# manual_motors.net
KiCad netlist of a schematic drawn in EAGLE
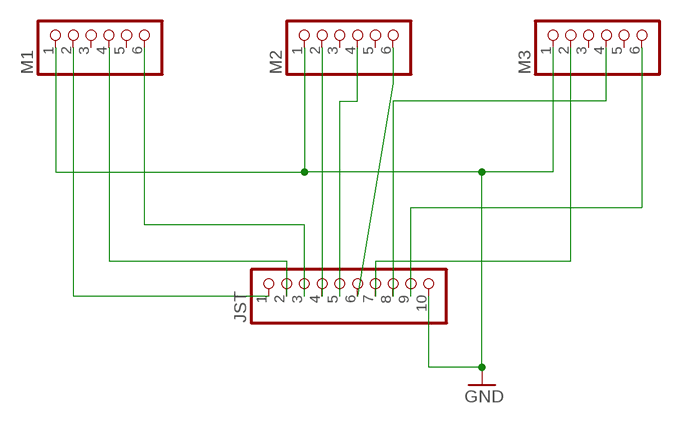
[diagram p0: schematic, sheet 1]

(export (version "E")
  (design (tool "Eeschema 10.0.6"))
  (components
    (comp (ref "JST")
      (value "PINHD-1X10")
      (footprint "eagle-import:1X10")
      (libsource (lib "eagle-import") (part "PINHD-1X10"))
    )
    (comp (ref "M1")
      (value "PINHD-1X6")
      (footprint "eagle-import:1X06")
      (libsource (lib "eagle-import") (part "PINHD-1X6"))
    )
    (comp (ref "M2")
      (value "PINHD-1X6")
      (footprint "eagle-import:1X06")
      (libsource (lib "eagle-import") (part "PINHD-1X6"))
    )
    (comp (ref "M3")
      (value "PINHD-1X6")
      (footprint "eagle-import:1X06")
      (libsource (lib "eagle-import") (part "PINHD-1X6"))
    )
  )
  (nets
    (net (code "1") (name "GND") (class "Default")
      (node (ref "JST") (pin "10") (pinfunction "10_10") (pintype "passive"))
      (node (ref "M1") (pin "1") (pinfunction "1_1") (pintype "passive"))
      (node (ref "M2") (pin "1") (pinfunction "1_1") (pintype "passive"))
      (node (ref "M3") (pin "1") (pinfunction "1_1") (pintype "passive"))
    )
    (net (code "2") (name "Net-(JST-Pad1)") (class "Default")
      (node (ref "JST") (pin "1") (pinfunction "1_1") (pintype "passive"))
      (node (ref "M1") (pin "2") (pinfunction "2_2") (pintype "passive"))
    )
    (net (code "3") (name "Net-(JST-Pad2)") (class "Default")
      (node (ref "JST") (pin "2") (pinfunction "2_2") (pintype "passive"))
      (node (ref "M1") (pin "4") (pinfunction "4_4") (pintype "passive"))
    )
    (net (code "4") (name "Net-(JST-Pad3)") (class "Default")
      (node (ref "JST") (pin "3") (pinfunction "3_3") (pintype "passive"))
      (node (ref "M1") (pin "6") (pinfunction "6_6") (pintype "passive"))
    )
    (net (code "5") (name "Net-(JST-Pad4)") (class "Default")
      (node (ref "JST") (pin "4") (pinfunction "4_4") (pintype "passive"))
      (node (ref "M2") (pin "2") (pinfunction "2_2") (pintype "passive"))
    )
    (net (code "6") (name "Net-(JST-Pad5)") (class "Default")
      (node (ref "JST") (pin "5") (pinfunction "5_5") (pintype "passive"))
      (node (ref "M2") (pin "4") (pinfunction "4_4") (pintype "passive"))
    )
    (net (code "7") (name "Net-(JST-Pad6)") (class "Default")
      (node (ref "JST") (pin "6") (pinfunction "6_6") (pintype "passive"))
      (node (ref "M2") (pin "6") (pinfunction "6_6") (pintype "passive"))
    )
    (net (code "8") (name "Net-(JST-Pad7)") (class "Default")
      (node (ref "JST") (pin "7") (pinfunction "7_7") (pintype "passive"))
      (node (ref "M3") (pin "2") (pinfunction "2_2") (pintype "passive"))
    )
    (net (code "9") (name "Net-(JST-Pad8)") (class "Default")
      (node (ref "JST") (pin "8") (pinfunction "8_8") (pintype "passive"))
      (node (ref "M3") (pin "4") (pinfunction "4_4") (pintype "passive"))
    )
    (net (code "10") (name "Net-(JST-Pad9)") (class "Default")
      (node (ref "JST") (pin "9") (pinfunction "9_9") (pintype "passive"))
      (node (ref "M3") (pin "6") (pinfunction "6_6") (pintype "passive"))
    )
    (net (code "11") (name "unconnected-(M1-Pad3)") (class "Default")
      (node (ref "M1") (pin "3") (pinfunction "3_3") (pintype "passive"))
    )
    (net (code "12") (name "unconnected-(M1-Pad5)") (class "Default")
      (node (ref "M1") (pin "5") (pinfunction "5_5") (pintype "passive"))
    )
    (net (code "13") (name "unconnected-(M2-Pad3)") (class "Default")
      (node (ref "M2") (pin "3") (pinfunction "3_3") (pintype "passive"))
    )
    (net (code "14") (name "unconnected-(M2-Pad5)") (class "Default")
      (node (ref "M2") (pin "5") (pinfunction "5_5") (pintype "passive"))
    )
    (net (code "15") (name "unconnected-(M3-Pad3)") (class "Default")
      (node (ref "M3") (pin "3") (pinfunction "3_3") (pintype "passive"))
    )
    (net (code "16") (name "unconnected-(M3-Pad5)") (class "Default")
      (node (ref "M3") (pin "5") (pinfunction "5_5") (pintype "passive"))
    )
  )
)
